# DRVS-SCHEMA.net
KiCad netlist of a schematic drawn in Altium Designer
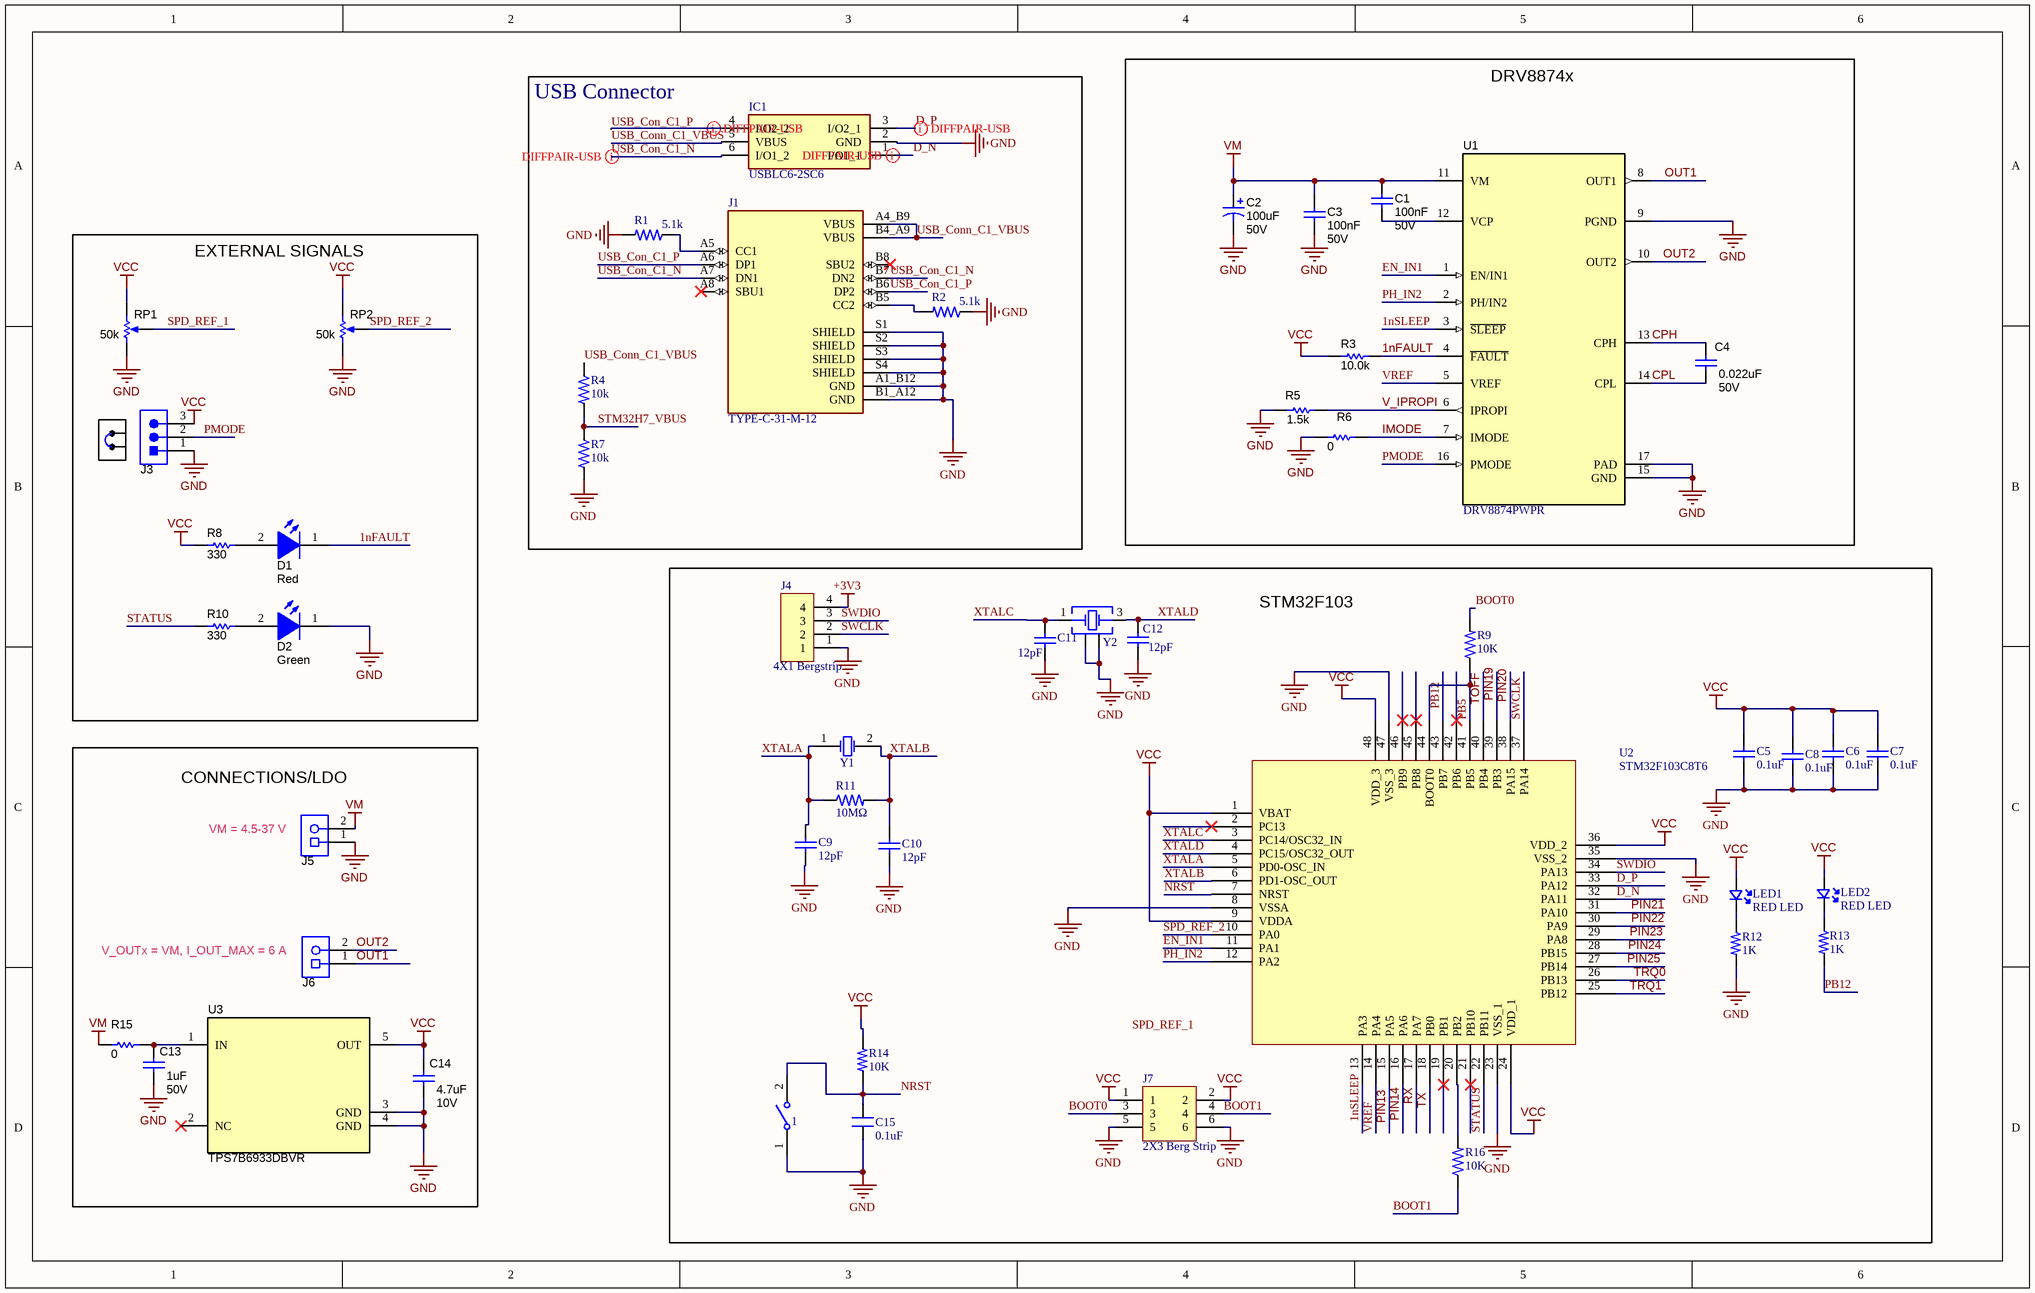
[diagram p0: DRVS-SCHEMA.SchDoc]

(export (version "E")
  (design (tool "Eeschema 10.0.6"))
  (components
    (comp (ref "1")
      (value "434113025826")
      (footprint "WS-TASV_L6W3.8H2.5_4341x30258x6")
      (description "WS-TASV J-Bend SMT Tact Switch, L6 x W3.8 x H2.5mm, 260g, SPST-NO, 12V, 50mA")
      (fields (field (name "MANUFACTURER") "Wurth Elektronik"))
      (libsource (lib "Dragino_xp") (part "BUTTON"))
    )
    (comp (ref "C1")
      (value "885012206095")
      (footprint "0603L")
      (description "CAP, CERM, 0.1 uF, 50 V, +/- 10%, X7R, 0603")
      (fields
        (field (name "MANUFACTURER") "Wurth Elektronik")
        (field (name "CAP_F") "100nF")
        (field (name "VDC_V") "50V")
        (field (name "PUBLISHER") "Texas Instruments")
      )
      (libsource (lib "drvs-motor") (part "CMP-0006837-4"))
    )
    (comp (ref "C2")
      (value "UBT1H101MPD1TD")
      (footprint "BT_1000x1250")
      (description "CAP, AL, 100 uF, 50 V, +/- 20%, TH")
      (fields
        (field (name "MANUFACTURER") "Nichicon")
        (field (name "VALUEDISPLAYED") "100uF")
        (field (name "VDC_V") "50V")
        (field (name "PUBLISHER") "Texas Instruments")
      )
      (libsource (lib "drvs-motor") (part "CMP-0009918-2"))
    )
    (comp (ref "C3")
      (value "885012206095")
      (footprint "0603L")
      (description "CAP, CERM, 0.1 uF, 50 V, +/- 10%, X7R, 0603")
      (fields
        (field (name "MANUFACTURER") "Wurth Elektronik")
        (field (name "CAP_F") "100nF")
        (field (name "VDC_V") "50V")
        (field (name "PUBLISHER") "Texas Instruments")
      )
      (libsource (lib "drvs-motor") (part "CMP-0006837-4"))
    )
    (comp (ref "C4")
      (value "885012206091")
      (footprint "0603L")
      (description "CAP, CERM, 0.022 uF, 50 V, +/- 10%, X7R, 0603")
      (fields
        (field (name "MANUFACTURER") "Wurth Elektronik")
        (field (name "VALUEDISPLAYED") "0.022uF")
        (field (name "VDC_V") "50V")
        (field (name "PUBLISHER") "Texas Instruments")
      )
      (libsource (lib "drvs-motor") (part "CMP-0006836-4"))
    )
    (comp (ref "C5")
      (value "0.1uF")
      (footprint "WCAP-CSST_0603_L1.6W0.8H0.8_Reflow")
      (fields
        (field (name "MANUFACTURER PART NUMBER") "885382206001")
        (field (name "MANUFACTURER") "Wurth Elektronik")
      )
      (libsource (lib "Dragino_xp") (part "0.1uF capacitor"))
    )
    (comp (ref "C6")
      (value "0.1uF")
      (footprint "WCAP-CSST_0603_L1.6W0.8H0.8_Reflow")
      (fields
        (field (name "MANUFACTURER PART NUMBER") "885382206001")
        (field (name "MANUFACTURER") "Wurth Elektronik")
      )
      (libsource (lib "Dragino_xp") (part "0.1uF capacitor"))
    )
    (comp (ref "C7")
      (value "0.1uF")
      (footprint "WCAP-CSST_0603_L1.6W0.8H0.8_Reflow")
      (fields
        (field (name "MANUFACTURER PART NUMBER") "885382206001")
        (field (name "MANUFACTURER") "Wurth Elektronik")
      )
      (libsource (lib "Dragino_xp") (part "0.1uF capacitor"))
    )
    (comp (ref "C8")
      (value "0.1uF")
      (footprint "WCAP-CSST_0603_L1.6W0.8H0.8_Reflow")
      (fields
        (field (name "MANUFACTURER PART NUMBER") "885382206001")
        (field (name "MANUFACTURER") "Wurth Elektronik")
      )
      (libsource (lib "Dragino_xp") (part "0.1uF capacitor"))
    )
    (comp (ref "C9")
      (value "12pF")
      (footprint "WCAP-CSST_0603_L1.6W0.8H0.8_Reflow")
      (fields
        (field (name "MANUFACTURER PART NUMBER") "885382206001")
        (field (name "MANUFACTURER") "Wurth Elektronik")
      )
      (libsource (lib "Dragino_xp") (part "0.1uF capacitor_4"))
    )
    (comp (ref "C10")
      (value "12pF")
      (footprint "WCAP-CSST_0603_L1.6W0.8H0.8_Reflow")
      (fields
        (field (name "MANUFACTURER PART NUMBER") "885382206001")
        (field (name "MANUFACTURER") "Wurth Elektronik")
      )
      (libsource (lib "Dragino_xp") (part "0.1uF capacitor_4"))
    )
    (comp (ref "C11")
      (value "12pF")
      (footprint "WCAP-CSST_0603_L1.6W0.8H0.8_Reflow")
      (fields
        (field (name "MANUFACTURER PART NUMBER") "885382206001")
        (field (name "MANUFACTURER") "Wurth Elektronik")
      )
      (libsource (lib "Dragino_xp") (part "0.1uF capacitor_4"))
    )
    (comp (ref "C12")
      (value "12pF")
      (footprint "WCAP-CSST_0603_L1.6W0.8H0.8_Reflow")
      (fields
        (field (name "MANUFACTURER PART NUMBER") "885382206001")
        (field (name "MANUFACTURER") "Wurth Elektronik")
      )
      (libsource (lib "Dragino_xp") (part "0.1uF capacitor_4"))
    )
    (comp (ref "C13")
      (value "885012207103")
      (footprint "0805L")
      (description "CAP, CERM, 1 uF, 50 V, +/- 10%, X7R, 0805")
      (fields
        (field (name "MANUFACTURER") "Wurth Elektronik")
        (field (name "VALUEDISPLAYED") "1uF")
        (field (name "VDC_V") "50V")
        (field (name "PUBLISHER") "Texas Instruments")
      )
      (libsource (lib "drvs-motor") (part "CMP-0007696-2"))
    )
    (comp (ref "C14")
      (value "C0603C475K8PACTU")
      (footprint "0603L")
      (description "CAP, CERM, 4.7 uF, 10 V, +/- 10%, X5R, 0603")
      (fields
        (field (name "MANUFACTURER") "Kemet")
        (field (name "VALUEDISPLAYED") "4.7uF")
        (field (name "VDC_V") "10V")
        (field (name "PUBLISHER") "Texas Instruments")
      )
      (libsource (lib "drvs-motor") (part "CMP-0006949-5"))
    )
    (comp (ref "C15")
      (value "0.1uF")
      (footprint "CAP_0805")
      (description "0.1µF ±5% 50V Ceramic Capacitor X7R 0805 (2012 Metric)")
      (fields
        (field (name "MANUFACTURER") "KEMET")
        (field (name "MANUFACTURING PART NUMBER") "C0805C104J5RACTU")
      )
      (libsource (lib "STM_SCH_LIB") (part "CAP_0.1uF-50V-5%-0805"))
    )
    (comp (ref "D1")
      (value "Red")
      (footprint "WL-SMCW_RED")
      (description "LED, Red, SMD")
      (fields
        (field (name "MANUFACTURER") "Wurth Elektronik")
        (field (name "PARTNUMBER") "150060RS75000")
        (field (name "PUBLISHER") "Texas Instruments")
      )
      (libsource (lib "drvs-motor") (part "CMP-0002947-2"))
    )
    (comp (ref "D2")
      (value "Green")
      (footprint "WL-SMCW_GREEN")
      (description "LED, Green, SMD")
      (fields
        (field (name "MANUFACTURER") "Wurth Elektronik")
        (field (name "PARTNUMBER") "150060VS75000")
        (field (name "PUBLISHER") "Texas Instruments")
      )
      (libsource (lib "drvs-motor") (part "CMP-0002894-1"))
    )
    (comp (ref "IC1")
      (value "USBLC6-2SC6")
      (footprint "SOT95P280X145-6N")
      (description "Integrated Circuit")
      (fields (field (name "MOUSER PART NUMBER") "511-USBLC6-2SC6"))
      (libsource (lib "Schlib1") (part "USBLC6-2SC6"))
    )
    (comp (ref "J1")
      (value "TYPE-C-31-M-12")
      (footprint "HRO_TYPE-C-31-M-12")
      (description "USB Connectors 24 Receptacle 1 8.94*7.3mm RoHS")
      (fields (field (name "MF") "HRO Electronics Co., Ltd."))
      (libsource (lib "Schlib1") (part "TYPE-C-31-M-12"))
    )
    (comp (ref "J3")
      (value "61300311121")
      (footprint "WURTH_61300311121")
      (description "Header, 2.54 mm, 3x1, Gold, TH")
      (fields (field (name "MANUFACTURER") "Wurth Elektronik") (field (name "PUBLISHER") "Texas Instruments"))
      (libsource (lib "drvs-motor") (part "CMP-0054796-1"))
    )
    (comp (ref "J4")
      (value "4X1 Bergstrip")
      (footprint "CON4_100_40D72_TH_ST_MALE")
      (description "4 pin, 1 row, 2.54mm pitch bergstrip")
      (fields (field (name "MANUFACTURER") "NA"))
      (libsource (lib "STM_SCH_LIB") (part "CON-BS-PLG_4X1-100-TH-ST"))
    )
    (comp (ref "J5")
      (value "CMP-0054828-1")
      (footprint "Wurth_691101710002")
      (description "Terminal Block, 5 mm, 2x1, Tin, TH")
      (fields
        (field (name "PARTNUMBER") "691 101 710 002")
        (field (name "MANUFACTURER") "Wurth Elektronik")
        (field (name "PUBLISHER") "Texas Instruments")
      )
      (libsource (lib "drvs-motor") (part "CMP-0054828-1"))
    )
    (comp (ref "J6")
      (value "CMP-0054828-1")
      (footprint "Wurth_691101710002")
      (description "Terminal Block, 5 mm, 2x1, Tin, TH")
      (fields
        (field (name "PARTNUMBER") "691 101 710 002")
        (field (name "MANUFACTURER") "Wurth Elektronik")
        (field (name "PUBLISHER") "Texas Instruments")
      )
      (libsource (lib "drvs-motor") (part "CMP-0054828-1"))
    )
    (comp (ref "J7")
      (value "2X3 Berg Strip")
      (footprint "CON6_100_59D78_TH_ST_Duplicate")
      (description "6 pin, 2 row, 2.54mm pitch bergstrip")
      (fields (field (name "MANUFACTURER") "NA"))
      (libsource (lib "STM_SCH_LIB") (part "CON-BS-PLG_2X3-100-TH-ST"))
    )
    (comp (ref "LED1")
      (value "RED LED")
      (footprint "LED_0805")
      (description "Red 621nm LED Indication - Discrete 2V 0805 (2012 Metric)")
      (fields
        (field (name "MANUFACTURER") "Lite-On Inc.")
        (field (name "MANUFACTURER PART NUMBER") "LTST-C170EKT")
      )
      (libsource (lib "STM_SCH_LIB") (part "LED-RED_10mA-0805"))
    )
    (comp (ref "LED2")
      (value "RED LED")
      (footprint "LED_0805")
      (description "Red 621nm LED Indication - Discrete 2V 0805 (2012 Metric)")
      (fields
        (field (name "MANUFACTURER") "Lite-On Inc.")
        (field (name "MANUFACTURER PART NUMBER") "LTST-C170EKT")
      )
      (libsource (lib "STM_SCH_LIB") (part "LED-RED_10mA-0805"))
    )
    (comp (ref "R1")
      (value "5.1k")
      (footprint "RESC2012X65N")
      (description "Fixed Resistors")
      (fields (field (name "MP") "CRG0805F33R") (field (name "MF") "TE Connectivity"))
      (libsource (lib "Schlib1") (part "resisitor"))
    )
    (comp (ref "R2")
      (value "5.1k")
      (footprint "RESC2012X65N")
      (description "Fixed Resistors")
      (fields (field (name "MP") "CRG0805F33R") (field (name "MF") "TE Connectivity"))
      (libsource (lib "Schlib1") (part "resisitor"))
    )
    (comp (ref "R3")
      (value "ERA-3ARW103V")
      (footprint "0603L")
      (description "RES, 10.0 k, 0.05%, 0.1 W, AEC-Q200 Grade 0, 0603")
      (fields (field (name "MANUFACTURER") "Panasonic") (field (name "VALUEDISPLAYED") "10.0k"))
      (libsource (lib "drvs-motor") (part "RES-10K-0603"))
    )
    (comp (ref "R4")
      (value "10k")
      (footprint "RESC2012X65N")
      (description "Fixed Resistors")
      (fields (field (name "MP") "CRG0805F33R") (field (name "MF") "TE Connectivity"))
      (libsource (lib "Schlib1") (part "resisitor"))
    )
    (comp (ref "R5")
      (value "CRCW06031K50JNEA")
      (footprint "0603L")
      (description "RES, 1.5 k, 5%, 0.1 W, AEC-Q200 Grade 0, 0603")
      (fields (field (name "MANUFACTURER") "Vishay-Dale") (field (name "VALUEDISPLAYED") "1.5k"))
      (libsource (lib "drvs-motor") (part "CMP-0025733-4"))
    )
    (comp (ref "R6")
      (value "ERJ-3GEY0R00V")
      (footprint "0603L")
      (description "RES, 0, 5%, 0.1 W, 0603")
      (fields
        (field (name "MANUFACTURER") "Panasonic")
        (field (name "VALUEDISPLAYED") "0")
        (field (name "PUBLISHER") "Texas Instruments")
      )
      (libsource (lib "drvs-motor") (part "CMP-0025874-3"))
    )
    (comp (ref "R7")
      (value "10k")
      (footprint "RESC2012X65N")
      (description "Fixed Resistors")
      (fields (field (name "MP") "CRG0805F33R") (field (name "MF") "TE Connectivity"))
      (libsource (lib "Schlib1") (part "resisitor"))
    )
    (comp (ref "R8")
      (value "CRCW0603330RJNEA")
      (footprint "0603L")
      (description "RES, 330, 5%, 0.1 W, AEC-Q200 Grade 0, 0603")
      (fields (field (name "MANUFACTURER") "Vishay-Dale") (field (name "VALUEDISPLAYED") "330"))
      (libsource (lib "drvs-motor") (part "CMP-0025785-4"))
    )
    (comp (ref "R9")
      (value "10K")
      (footprint "RESC2012X65N")
      (description "Fixed Resistors")
      (fields (field (name "MP") "CRG0805F33R") (field (name "MF") "TE Connectivity"))
      (libsource (lib "Dragino_xp") (part "resisitor_3"))
    )
    (comp (ref "R10")
      (value "CRCW0603330RJNEA")
      (footprint "0603L")
      (description "RES, 330, 5%, 0.1 W, AEC-Q200 Grade 0, 0603")
      (fields (field (name "MANUFACTURER") "Vishay-Dale") (field (name "VALUEDISPLAYED") "330"))
      (libsource (lib "drvs-motor") (part "CMP-0025785-4"))
    )
    (comp (ref "R11")
      (value "10MΩ")
      (footprint "RESC2012X65N")
      (description "Fixed Resistors")
      (fields (field (name "MP") "CRG0805F33R") (field (name "MF") "TE Connectivity"))
      (libsource (lib "Dragino_xp") (part "resisitor_3"))
    )
    (comp (ref "R12")
      (value "1K")
      (footprint "RES_0805")
      (description "1 kOhms ±1% 0.125W, 1/8W Chip Resistor 0805 (2012 Metric) Moisture Resistant Thick Film")
      (fields (field (name "MANUFACTURER") "垈㎵á") (field (name "MANUFACTURER PART NUMBER") "RC0805FR-071KL"))
      (libsource (lib "STM_SCH_LIB") (part "RES_1K-0.125W-1%-0805"))
    )
    (comp (ref "R13")
      (value "1K")
      (footprint "RES_0805")
      (description "1 kOhms ±1% 0.125W, 1/8W Chip Resistor 0805 (2012 Metric) Moisture Resistant Thick Film")
      (fields (field (name "MANUFACTURER") "垈㎵á") (field (name "MANUFACTURER PART NUMBER") "RC0805FR-071KL"))
      (libsource (lib "STM_SCH_LIB") (part "RES_1K-0.125W-1%-0805"))
    )
    (comp (ref "R14")
      (value "10K")
      (footprint "RES_0805")
      (description "10 kOhms ±1% 0.125W, 1/8W Chip Resistor 0805 (2012 Metric) Moisture Resistant Thick Film")
      (fields
        (field (name "MANUFACTURER") "Yageo")
        (field (name "MANUFACTURING PART NUMBER") "RC0805FR-0710KL")
      )
      (libsource (lib "STM_SCH_LIB") (part "RES_10K-0.125W-1%-0805"))
    )
    (comp (ref "R15")
      (value "ERJ-3GEY0R00V")
      (footprint "0603L")
      (description "RES, 0, 5%, 0.1 W, 0603")
      (fields
        (field (name "MANUFACTURER") "Panasonic")
        (field (name "VALUEDISPLAYED") "0")
        (field (name "PUBLISHER") "Texas Instruments")
      )
      (libsource (lib "drvs-motor") (part "CMP-0025874-3"))
    )
    (comp (ref "R16")
      (value "10K")
      (footprint "RESC2012X65N")
      (description "Fixed Resistors")
      (fields (field (name "MP") "CRG0805F33R") (field (name "MF") "TE Connectivity"))
      (libsource (lib "Dragino_xp") (part "resisitor_3"))
    )
    (comp (ref "RP1")
      (value "50k")
      (footprint "Bourns_3352T")
      (description "Trimming Potentiometer, 50K, 0.5W, TH")
      (fields
        (field (name "MANUFACTURER") "Bourns")
        (field (name "PARTNUMBER") "3352T-1-503LF")
        (field (name "PUBLISHER") "Texas Instruments")
      )
      (libsource (lib "drvs-motor") (part "CMP-0001777-2"))
    )
    (comp (ref "RP2")
      (value "50k")
      (footprint "Bourns_3352T")
      (description "Trimming Potentiometer, 50K, 0.5W, TH")
      (fields
        (field (name "MANUFACTURER") "Bourns")
        (field (name "PARTNUMBER") "3352T-1-503LF")
        (field (name "PUBLISHER") "Texas Instruments")
      )
      (libsource (lib "drvs-motor") (part "CMP-0001777-2"))
    )
    (comp (ref "SH-J1")
      (value "60900213421")
      (footprint "Wurth_60900213421")
      (description "Shunt, 2.54mm, Gold, Black")
      (fields (field (name "MANUFACTURER") "Wurth Elektronik") (field (name "PUBLISHER") "Texas Instruments"))
      (libsource (lib "drvs-motor") (part "CMP-0003761-1"))
    )
    (comp (ref "U1")
      (value "DRV8874PWPR")
      (footprint "PWP0016J_N")
      (description "H-Bridge Motor Drivers With Integrated Current Sense and Regulation, PWP0016J (HTSSOP-16)")
      (fields
        (field (name "ALTERNATE PARTNUMBER") "DRV8874PWP")
        (field (name "MANUFACTURER") "Texas Instruments")
        (field (name "PARTNUMBER") "DRV8874PWPR")
      )
      (libsource (lib "drvs-motor") (part "CMP-0081845-1"))
    )
    (comp (ref "U2")
      (value "STM32F103C8T6")
      (footprint "LQFP-48_19.6_393_58X11_SMD")
      (description "ARM® Cortex®-M3 STM32F1 Microcontroller IC 32-Bit 72MHz 64KB (64K x 8) FLASH")
      (fields (field (name "MANUFACTURER") "STMicroelectronics"))
      (libsource (lib "STM_SCH_LIB") (part "IC-STM32F103C8T6 _1"))
    )
    (comp (ref "U3")
      (value "TPS7B6933DBVR")
      (footprint "DBV0005A_N")
      (description "40-V Ultralow-Iq Low-Dropout Regulator, DBV0005A (SOT-23-5)")
      (fields (field (name "MANUFACTURER") "Texas Instruments") (field (name "PARTNUMBER") "TPS7B6933DBVR"))
      (libsource (lib "drvs-motor") (part "CMP-0077328-2"))
    )
    (comp (ref "Y1")
      (value "32.768kHz")
      (footprint "WE-XTAL_IQXC-25")
      (description "WE-XTAL Watch Crystal, SMT, IQXC-25, 32.768kHz, +/-10ppm")
      (fields
        (field (name "MANUFACTURER PART NUMBER") "830062558")
        (field (name "MANUFACTURER") "Wurth Elektronik")
      )
      (libsource (lib "Dragino_xp") (part "CRYSTAL 32.768kH"))
    )
    (comp (ref "Y2")
      (value "25MHz")
      (footprint "WE-XTAL_CFPX-180")
      (description "WE-XTAL Quartz Crystal, SMT, CFPX-180, 25MHz, +/-10ppm")
      (fields
        (field (name "MANUFACTURER PART NUMBER") "830108174209")
        (field (name "MANUFACTURER") "Wurth Elektronik")
      )
      (libsource (lib "Dragino_xp") (part "Crystals"))
    )
  )
  (nets
    (net (code "1") (name "+3V3") (class "Default")
      (node (ref "J4") (pin "4") (pinfunction "4_4") (pintype "passive"))
    )
    (net (code "2") (name "/1nFAULT") (class "Default")
      (node (ref "D1") (pin "1") (pinfunction "K_1") (pintype "passive"))
      (node (ref "R3") (pin "2") (pinfunction "2_2") (pintype "passive"))
      (node (ref "U1") (pin "4") (pinfunction "FAULT_4") (pintype "open_collector"))
    )
    (net (code "3") (name "/1nSLEEP") (class "Default")
      (node (ref "U1") (pin "3") (pinfunction "SLEEP_3") (pintype "input"))
      (node (ref "U2") (pin "13") (pinfunction "PA3_13") (pintype "passive"))
    )
    (net (code "4") (name "/BOOT0") (class "Default")
      (node (ref "J7") (pin "3") (pinfunction "3_3") (pintype "passive"))
      (node (ref "R9") (pin "2") (pinfunction "2_2") (pintype "passive"))
    )
    (net (code "5") (name "/BOOT1") (class "Default")
      (node (ref "J7") (pin "4") (pinfunction "4_4") (pintype "passive"))
      (node (ref "R16") (pin "1") (pinfunction "1_1") (pintype "passive"))
    )
    (net (code "6") (name "/CPH") (class "Default")
      (node (ref "C4") (pin "1") (pinfunction "1_1") (pintype "passive"))
      (node (ref "U1") (pin "13") (pinfunction "CPH_13") (pintype "power_in"))
    )
    (net (code "7") (name "/CPL") (class "Default")
      (node (ref "C4") (pin "2") (pinfunction "2_2") (pintype "passive"))
      (node (ref "U1") (pin "14") (pinfunction "CPL_14") (pintype "power_in"))
    )
    (net (code "8") (name "/D_N") (class "Default")
      (node (ref "IC1") (pin "1") (pinfunction "I/O1_1_1") (pintype "passive"))
      (node (ref "U2") (pin "32") (pinfunction "PA11_32") (pintype "passive"))
    )
    (net (code "9") (name "/D_P") (class "Default")
      (node (ref "IC1") (pin "3") (pinfunction "I/O2_1_3") (pintype "passive"))
      (node (ref "U2") (pin "33") (pinfunction "PA12_33") (pintype "passive"))
    )
    (net (code "10") (name "/EN_IN1") (class "Default")
      (node (ref "U1") (pin "1") (pinfunction "EN/IN1_1") (pintype "input"))
      (node (ref "U2") (pin "11") (pinfunction "PA1_11") (pintype "passive"))
    )
    (net (code "11") (name "/IMODE") (class "Default")
      (node (ref "R6") (pin "2") (pinfunction "2_2") (pintype "passive"))
      (node (ref "U1") (pin "7") (pinfunction "IMODE_7") (pintype "input"))
    )
    (net (code "12") (name "/NRST") (class "Default")
      (node (ref "1") (pin "2") (pinfunction "2_2") (pintype "passive"))
      (node (ref "C15") (pin "2") (pinfunction "2_2") (pintype "passive"))
      (node (ref "R14") (pin "1") (pinfunction "1_1") (pintype "passive"))
      (node (ref "U2") (pin "7") (pinfunction "NRST_7") (pintype "passive"))
    )
    (net (code "13") (name "/OUT1") (class "Default")
      (node (ref "J6") (pin "1") (pinfunction "1_1") (pintype "passive"))
      (node (ref "U1") (pin "8") (pinfunction "OUT1_8") (pintype "output"))
    )
    (net (code "14") (name "/OUT2") (class "Default")
      (node (ref "J6") (pin "2") (pinfunction "2_2") (pintype "passive"))
      (node (ref "U1") (pin "10") (pinfunction "OUT2_10") (pintype "output"))
    )
    (net (code "15") (name "/PB5") (class "Default")
      (node (ref "R9") (pin "1") (pinfunction "1_1") (pintype "passive"))
      (node (ref "U2") (pin "41") (pinfunction "PB5_41") (pintype "passive"))
      (node (ref "U2") (pin "44") (pinfunction "BOOT0_44") (pintype "passive"))
    )
    (net (code "16") (name "/PB12") (class "Default")
      (node (ref "R13") (pin "1") (pinfunction "1_1") (pintype "passive"))
      (node (ref "U2") (pin "43") (pinfunction "PB7_43") (pintype "passive"))
    )
    (net (code "17") (name "/PH_IN2") (class "Default")
      (node (ref "U1") (pin "2") (pinfunction "PH/IN2_2") (pintype "input"))
      (node (ref "U2") (pin "12") (pinfunction "PA2_12") (pintype "passive"))
    )
    (net (code "18") (name "/PIN13") (class "Default")
      (node (ref "U2") (pin "15") (pinfunction "PA5_15") (pintype "passive"))
    )
    (net (code "19") (name "/PIN14") (class "Default")
      (node (ref "U2") (pin "16") (pinfunction "PA6_16") (pintype "passive"))
    )
    (net (code "20") (name "/PIN19") (class "Default")
      (node (ref "U2") (pin "39") (pinfunction "PB3_39") (pintype "passive"))
    )
    (net (code "21") (name "/PIN20") (class "Default")
      (node (ref "U2") (pin "38") (pinfunction "PA15_38") (pintype "passive"))
    )
    (net (code "22") (name "/PIN21") (class "Default")
      (node (ref "U2") (pin "31") (pinfunction "PA10_31") (pintype "passive"))
    )
    (net (code "23") (name "/PIN22") (class "Default")
      (node (ref "U2") (pin "30") (pinfunction "PA9_30") (pintype "passive"))
    )
    (net (code "24") (name "/PIN23") (class "Default")
      (node (ref "U2") (pin "29") (pinfunction "PA8_29") (pintype "passive"))
    )
    (net (code "25") (name "/PIN24") (class "Default")
      (node (ref "U2") (pin "28") (pinfunction "PB15_28") (pintype "passive"))
    )
    (net (code "26") (name "/PIN25") (class "Default")
      (node (ref "U2") (pin "27") (pinfunction "PB14_27") (pintype "passive"))
    )
    (net (code "27") (name "/PMODE") (class "Default")
      (node (ref "J3") (pin "2") (pinfunction "2_2") (pintype "passive"))
      (node (ref "U1") (pin "16") (pinfunction "PMODE_16") (pintype "input"))
    )
    (net (code "28") (name "/RX") (class "Default")
      (node (ref "U2") (pin "17") (pinfunction "PA7_17") (pintype "passive"))
    )
    (net (code "29") (name "/SPD_REF_1") (class "Default")
      (node (ref "RP1") (pin "2") (pinfunction "WIPER_2") (pintype "passive"))
    )
    (net (code "30") (name "/SPD_REF_2") (class "Default")
      (node (ref "RP2") (pin "2") (pinfunction "WIPER_2") (pintype "passive"))
      (node (ref "U2") (pin "10") (pinfunction "PA0_10") (pintype "passive"))
    )
    (net (code "31") (name "/STATUS") (class "Default")
      (node (ref "R10") (pin "1") (pinfunction "1_1") (pintype "passive"))
      (node (ref "U2") (pin "22") (pinfunction "PB11_22") (pintype "passive"))
    )
    (net (code "32") (name "/STM32H7_VBUS") (class "Default")
      (node (ref "R4") (pin "2") (pinfunction "2_2") (pintype "passive"))
      (node (ref "R7") (pin "1") (pinfunction "1_1") (pintype "passive"))
    )
    (net (code "33") (name "/SWCLK") (class "Default")
      (node (ref "J4") (pin "2") (pinfunction "2_2") (pintype "passive"))
      (node (ref "U2") (pin "37") (pinfunction "PA14_37") (pintype "passive"))
    )
    (net (code "34") (name "/SWDIO") (class "Default")
      (node (ref "J4") (pin "3") (pinfunction "3_3") (pintype "passive"))
      (node (ref "U2") (pin "34") (pinfunction "PA13_34") (pintype "passive"))
    )
    (net (code "35") (name "/TOFF") (class "Default")
      (node (ref "U2") (pin "40") (pinfunction "PB4_40") (pintype "passive"))
    )
    (net (code "36") (name "/TRQ0") (class "Default")
      (node (ref "U2") (pin "26") (pinfunction "PB13_26") (pintype "passive"))
    )
    (net (code "37") (name "/TRQ1") (class "Default")
      (node (ref "U2") (pin "25") (pinfunction "PB12_25") (pintype "passive"))
    )
    (net (code "38") (name "/TX") (class "Default")
      (node (ref "U2") (pin "18") (pinfunction "PB0_18") (pintype "passive"))
    )
    (net (code "39") (name "/USB_Con_C1_N") (class "Default")
      (node (ref "IC1") (pin "6") (pinfunction "I/O1_2_6") (pintype "passive"))
      (node (ref "J1") (pin "A7") (pinfunction "DN1_A7") (pintype "bidirectional"))
      (node (ref "J1") (pin "B7") (pinfunction "DN2_B7") (pintype "bidirectional"))
    )
    (net (code "40") (name "/USB_Con_C1_P") (class "Default")
      (node (ref "IC1") (pin "4") (pinfunction "I/O2_2_4") (pintype "passive"))
      (node (ref "J1") (pin "A6") (pinfunction "DP1_A6") (pintype "bidirectional"))
      (node (ref "J1") (pin "B6") (pinfunction "DP2_B6") (pintype "bidirectional"))
    )
    (net (code "41") (name "/USB_Conn_C1_VBUS") (class "Default")
      (node (ref "IC1") (pin "5") (pinfunction "VBUS_5") (pintype "passive"))
      (node (ref "J1") (pin "A4_B9") (pinfunction "VBUS_A4_B9") (pintype "power_in"))
      (node (ref "J1") (pin "B4_A9") (pinfunction "VBUS_B4_A9") (pintype "power_in"))
      (node (ref "R4") (pin "1") (pinfunction "1_1") (pintype "passive"))
    )
    (net (code "42") (name "/VREF") (class "Default")
      (node (ref "U1") (pin "5") (pinfunction "VREF_5") (pintype "power_in"))
      (node (ref "U2") (pin "14") (pinfunction "PA4_14") (pintype "passive"))
    )
    (net (code "43") (name "/V_IPROPI") (class "Default")
      (node (ref "R5") (pin "2") (pinfunction "2_2") (pintype "passive"))
      (node (ref "U1") (pin "6") (pinfunction "IPROPI_6") (pintype "output"))
    )
    (net (code "44") (name "/XTALA") (class "Default")
      (node (ref "C9") (pin "2") (pinfunction "2_2") (pintype "passive"))
      (node (ref "R11") (pin "1") (pinfunction "1_1") (pintype "passive"))
      (node (ref "U2") (pin "5") (pinfunction "PD0-OSC_IN_5") (pintype "passive"))
      (node (ref "Y1") (pin "1") (pinfunction "OSC1_1") (pintype "passive"))
    )
    (net (code "45") (name "/XTALB") (class "Default")
      (node (ref "C10") (pin "2") (pinfunction "2_2") (pintype "passive"))
      (node (ref "R11") (pin "2") (pinfunction "2_2") (pintype "passive"))
      (node (ref "U2") (pin "6") (pinfunction "PD1-OSC_OUT_6") (pintype "passive"))
      (node (ref "Y1") (pin "2") (pinfunction "OSC2_2") (pintype "passive"))
    )
    (net (code "46") (name "/XTALC") (class "Default")
      (node (ref "C11") (pin "2") (pinfunction "2_2") (pintype "passive"))
      (node (ref "U2") (pin "3") (pinfunction "PC14/OSC32_IN_3") (pintype "passive"))
      (node (ref "Y2") (pin "1") (pinfunction "Crystal_1") (pintype "passive"))
    )
    (net (code "47") (name "/XTALD") (class "Default")
      (node (ref "C12") (pin "2") (pinfunction "2_2") (pintype "passive"))
      (node (ref "U2") (pin "4") (pinfunction "PC15/OSC32_OUT_4") (pintype "passive"))
      (node (ref "Y2") (pin "3") (pinfunction "Crystal_3") (pintype "passive"))
    )
    (net (code "48") (name "GND") (class "Default")
      (node (ref "1") (pin "1") (pinfunction "1_1") (pintype "passive"))
      (node (ref "C10") (pin "1") (pinfunction "1_1") (pintype "passive"))
      (node (ref "C11") (pin "1") (pinfunction "1_1") (pintype "passive"))
      (node (ref "C12") (pin "1") (pinfunction "1_1") (pintype "passive"))
      (node (ref "C13") (pin "2") (pinfunction "2_2") (pintype "passive"))
      (node (ref "C14") (pin "2") (pinfunction "2_2") (pintype "passive"))
      (node (ref "C15") (pin "1") (pinfunction "1_1") (pintype "passive"))
      (node (ref "C2") (pin "2") (pinfunction "-_2") (pintype "passive"))
      (node (ref "C3") (pin "2") (pinfunction "2_2") (pintype "passive"))
      (node (ref "C5") (pin "1") (pinfunction "1_1") (pintype "passive"))
      (node (ref "C6") (pin "1") (pinfunction "1_1") (pintype "passive"))
      (node (ref "C7") (pin "1") (pinfunction "1_1") (pintype "passive"))
      (node (ref "C8") (pin "1") (pinfunction "1_1") (pintype "passive"))
      (node (ref "C9") (pin "1") (pinfunction "1_1") (pintype "passive"))
      (node (ref "D2") (pin "1") (pinfunction "K_1") (pintype "passive"))
      (node (ref "IC1") (pin "2") (pinfunction "GND_2") (pintype "passive"))
      (node (ref "J1") (pin "A1_B12") (pinfunction "GND_A1_B12") (pintype "power_in"))
      (node (ref "J1") (pin "B1_A12") (pinfunction "GND_B1_A12") (pintype "power_in"))
      (node (ref "J1") (pin "S1") (pinfunction "SHIELD_S1") (pintype "passive"))
      (node (ref "J1") (pin "S2") (pinfunction "SHIELD_S2") (pintype "passive"))
      (node (ref "J1") (pin "S3") (pinfunction "SHIELD_S3") (pintype "passive"))
      (node (ref "J1") (pin "S4") (pinfunction "SHIELD_S4") (pintype "passive"))
      (node (ref "J3") (pin "1") (pinfunction "1_1") (pintype "passive"))
      (node (ref "J4") (pin "1") (pinfunction "1_1") (pintype "passive"))
      (node (ref "J5") (pin "1") (pinfunction "1_1") (pintype "passive"))
      (node (ref "J7") (pin "5") (pinfunction "5_5") (pintype "passive"))
      (node (ref "J7") (pin "6") (pinfunction "6_6") (pintype "passive"))
      (node (ref "R1") (pin "2") (pinfunction "2_2") (pintype "passive"))
      (node (ref "R12") (pin "1") (pinfunction "1_1") (pintype "passive"))
      (node (ref "R2") (pin "1") (pinfunction "1_1") (pintype "passive"))
      (node (ref "R5") (pin "1") (pinfunction "1_1") (pintype "passive"))
      (node (ref "R6") (pin "1") (pinfunction "1_1") (pintype "passive"))
      (node (ref "R7") (pin "2") (pinfunction "2_2") (pintype "passive"))
      (node (ref "RP1") (pin "1") (pinfunction "CCW_1") (pintype "passive"))
      (node (ref "RP2") (pin "1") (pinfunction "CCW_1") (pintype "passive"))
      (node (ref "U1") (pin "15") (pinfunction "GND_15") (pintype "power_in"))
      (node (ref "U1") (pin "17") (pinfunction "PAD_17") (pintype "power_in"))
      (node (ref "U1") (pin "9") (pinfunction "PGND_9") (pintype "power_in"))
      (node (ref "U2") (pin "23") (pinfunction "VSS_1_23") (pintype "passive"))
      (node (ref "U2") (pin "35") (pinfunction "VSS_2_35") (pintype "passive"))
      (node (ref "U2") (pin "47") (pinfunction "VSS_3_47") (pintype "passive"))
      (node (ref "U2") (pin "8") (pinfunction "VSSA_8") (pintype "passive"))
      (node (ref "U3") (pin "3") (pinfunction "GND_3") (pintype "power_in"))
      (node (ref "U3") (pin "4") (pinfunction "GND_4") (pintype "power_in"))
      (node (ref "Y2") (pin "2") (pinfunction "GND&Lid_2") (pintype "passive"))
      (node (ref "Y2") (pin "4") (pinfunction "GND&Lid_4") (pintype "passive"))
    )
    (net (code "49") (name "Net-(D1-A)") (class "Default")
      (node (ref "D1") (pin "2") (pinfunction "A_2") (pintype "passive"))
      (node (ref "R8") (pin "2") (pinfunction "2_2") (pintype "passive"))
    )
    (net (code "50") (name "Net-(D2-A)") (class "Default")
      (node (ref "D2") (pin "2") (pinfunction "A_2") (pintype "passive"))
      (node (ref "R10") (pin "2") (pinfunction "2_2") (pintype "passive"))
    )
    (net (code "51") (name "Net-(J1-CC1)") (class "Default")
      (node (ref "J1") (pin "A5") (pinfunction "CC1_A5") (pintype "bidirectional"))
      (node (ref "R1") (pin "1") (pinfunction "1_1") (pintype "passive"))
    )
    (net (code "52") (name "Net-(J1-CC2)") (class "Default")
      (node (ref "J1") (pin "B5") (pinfunction "CC2_B5") (pintype "bidirectional"))
      (node (ref "R2") (pin "2") (pinfunction "2_2") (pintype "passive"))
    )
    (net (code "53") (name "Net-(LED1-PadK)") (class "Default")
      (node (ref "LED1") (pin "K") (pinfunction "K_K") (pintype "passive"))
      (node (ref "R12") (pin "2") (pinfunction "2_2") (pintype "passive"))
    )
    (net (code "54") (name "Net-(LED2-PadK)") (class "Default")
      (node (ref "LED2") (pin "K") (pinfunction "K_K") (pintype "passive"))
      (node (ref "R13") (pin "2") (pinfunction "2_2") (pintype "passive"))
    )
    (net (code "55") (name "Net-(U1-VCP)") (class "Default")
      (node (ref "C1") (pin "2") (pinfunction "2_2") (pintype "passive"))
      (node (ref "U1") (pin "12") (pinfunction "VCP_12") (pintype "power_in"))
    )
    (net (code "56") (name "Net-(U2-PB2)") (class "Default")
      (node (ref "R16") (pin "2") (pinfunction "2_2") (pintype "passive"))
      (node (ref "U2") (pin "20") (pinfunction "PB2_20") (pintype "passive"))
    )
    (net (code "57") (name "Net-(U3-IN)") (class "Default")
      (node (ref "C13") (pin "1") (pinfunction "1_1") (pintype "passive"))
      (node (ref "R15") (pin "2") (pinfunction "2_2") (pintype "passive"))
      (node (ref "U3") (pin "1") (pinfunction "IN_1") (pintype "power_in"))
    )
    (net (code "58") (name "VCC") (class "Default")
      (node (ref "C14") (pin "1") (pinfunction "1_1") (pintype "passive"))
      (node (ref "C5") (pin "2") (pinfunction "2_2") (pintype "passive"))
      (node (ref "C6") (pin "2") (pinfunction "2_2") (pintype "passive"))
      (node (ref "C7") (pin "2") (pinfunction "2_2") (pintype "passive"))
      (node (ref "C8") (pin "2") (pinfunction "2_2") (pintype "passive"))
      (node (ref "J3") (pin "3") (pinfunction "3_3") (pintype "passive"))
      (node (ref "J7") (pin "1") (pinfunction "1_1") (pintype "passive"))
      (node (ref "J7") (pin "2") (pinfunction "2_2") (pintype "passive"))
      (node (ref "LED1") (pin "A") (pinfunction "A_A") (pintype "passive"))
      (node (ref "LED2") (pin "A") (pinfunction "A_A") (pintype "passive"))
      (node (ref "R14") (pin "2") (pinfunction "2_2") (pintype "passive"))
      (node (ref "R3") (pin "1") (pinfunction "1_1") (pintype "passive"))
      (node (ref "R8") (pin "1") (pinfunction "1_1") (pintype "passive"))
      (node (ref "RP1") (pin "3") (pinfunction "CW_3") (pintype "passive"))
      (node (ref "RP2") (pin "3") (pinfunction "CW_3") (pintype "passive"))
      (node (ref "U2") (pin "1") (pinfunction "VBAT_1") (pintype "passive"))
      (node (ref "U2") (pin "24") (pinfunction "VDD_1_24") (pintype "passive"))
      (node (ref "U2") (pin "36") (pinfunction "VDD_2_36") (pintype "passive"))
      (node (ref "U2") (pin "48") (pinfunction "VDD_3_48") (pintype "passive"))
      (node (ref "U2") (pin "9") (pinfunction "VDDA_9") (pintype "passive"))
      (node (ref "U3") (pin "5") (pinfunction "OUT_5") (pintype "power_in"))
    )
    (net (code "59") (name "VM") (class "Default")
      (node (ref "C1") (pin "1") (pinfunction "1_1") (pintype "passive"))
      (node (ref "C2") (pin "1") (pinfunction "+_1") (pintype "passive"))
      (node (ref "C3") (pin "1") (pinfunction "1_1") (pintype "passive"))
      (node (ref "J5") (pin "2") (pinfunction "2_2") (pintype "passive"))
      (node (ref "R15") (pin "1") (pinfunction "1_1") (pintype "passive"))
      (node (ref "U1") (pin "11") (pinfunction "VM_11") (pintype "power_in"))
    )
    (net (code "60") (name "unconnected-(J1-SBU1-PadA8)") (class "Default")
      (node (ref "J1") (pin "A8") (pinfunction "SBU1_A8") (pintype "bidirectional+no_connect"))
    )
    (net (code "61") (name "unconnected-(J1-SBU2-PadB8)") (class "Default")
      (node (ref "J1") (pin "B8") (pinfunction "SBU2_B8") (pintype "bidirectional+no_connect"))
    )
    (net (code "62") (name "unconnected-(U2-PB1-Pad19)") (class "Default")
      (node (ref "U2") (pin "19") (pinfunction "PB1_19") (pintype "passive+no_connect"))
    )
    (net (code "63") (name "unconnected-(U2-PB6-Pad42)") (class "Default")
      (node (ref "U2") (pin "42") (pinfunction "PB6_42") (pintype "passive+no_connect"))
    )
    (net (code "64") (name "unconnected-(U2-PB8-Pad45)") (class "Default")
      (node (ref "U2") (pin "45") (pinfunction "PB8_45") (pintype "passive+no_connect"))
    )
    (net (code "65") (name "unconnected-(U2-PB9-Pad46)") (class "Default")
      (node (ref "U2") (pin "46") (pinfunction "PB9_46") (pintype "passive+no_connect"))
    )
    (net (code "66") (name "unconnected-(U2-PB10-Pad21)") (class "Default")
      (node (ref "U2") (pin "21") (pinfunction "PB10_21") (pintype "passive+no_connect"))
    )
    (net (code "67") (name "unconnected-(U2-PC13-Pad2)") (class "Default")
      (node (ref "U2") (pin "2") (pinfunction "PC13_2") (pintype "passive+no_connect"))
    )
    (net (code "68") (name "unconnected-(U3-NC-Pad2)") (class "Default")
      (node (ref "U3") (pin "2") (pinfunction "NC_2") (pintype "passive+no_connect"))
    )
  )
)
